# SD_Card.net
KiCad netlist of a schematic drawn in Altium Designer
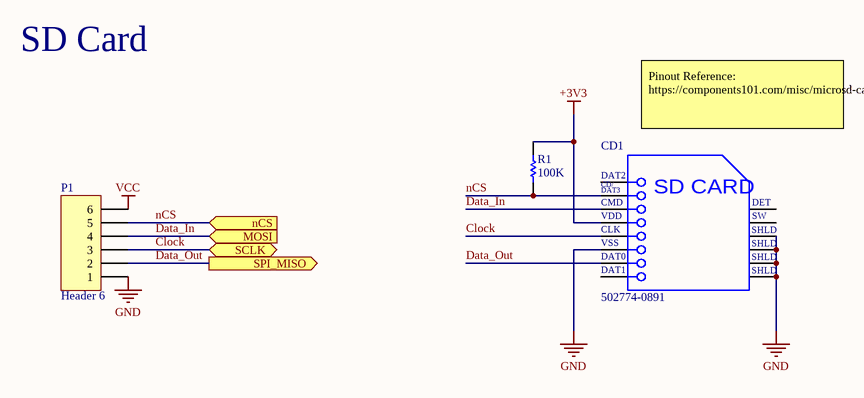
[diagram p0: SD_Card.SchDoc]

(export (version "E")
  (design (tool "Eeschema 10.0.6"))
  (components
    (comp (ref "CD1")
      (value "502774-0891")
      (footprint "MOLX-502774-0891_V")
      (description "Micro SD Memory Card Connector, 0.5 A, 10 V (DC), -25 to 85 degC, 8-Pin SMT, RoHS, Tape and Reel")
      (fields (field (name "MANUFACTURER") "Molex"))
      (libsource (lib "Altium Content Vault") (part "CN-SD-8-2SW-4S_B"))
    )
    (comp (ref "P1")
      (value "Header 6")
      (footprint "HDR1X6")
      (description "Header, 6-Pin")
      (fields (field (name "PUBLISHER") "Altium Limited"))
      (libsource (lib "Miscellaneous Connectors") (part "Header 6"))
    )
    (comp (ref "R1")
      (value "100K")
      (footprint "RESC1608X55X25ML10T15")
      (description "Chip Resistor, 100 KOhm, +/- 1%, 0.1 W, -55 to 155 degC, 0603 (1608 Metric), RoHS, Tape and Reel")
      (fields (field (name "MANUFACTURER") "Yageo") (field (name "TOLERANCE") "1%"))
      (libsource (lib "Altium Content Vault") (part "RES-2"))
    )
  )
  (nets
    (net (code "1") (name "+3V3") (class "Default")
      (node (ref "CD1") (pin "4") (pinfunction "VDD_4") (pintype "passive"))
      (node (ref "R1") (pin "2") (pinfunction "2_2") (pintype "passive"))
    )
    (net (code "2") (name "/Clock") (class "Default")
      (node (ref "CD1") (pin "5") (pinfunction "CLK_5") (pintype "passive"))
      (node (ref "P1") (pin "3") (pinfunction "3_3") (pintype "passive"))
    )
    (net (code "3") (name "/Data_In") (class "Default")
      (node (ref "CD1") (pin "3") (pinfunction "CMD_3") (pintype "passive"))
      (node (ref "P1") (pin "4") (pinfunction "4_4") (pintype "passive"))
    )
    (net (code "4") (name "/Data_Out") (class "Default")
      (node (ref "CD1") (pin "7") (pinfunction "DAT0_7") (pintype "passive"))
      (node (ref "P1") (pin "2") (pinfunction "2_2") (pintype "passive"))
    )
    (net (code "5") (name "/nCS") (class "Default")
      (node (ref "CD1") (pin "2") (pinfunction "CD/DAT3_2") (pintype "passive"))
      (node (ref "P1") (pin "5") (pinfunction "5_5") (pintype "passive"))
      (node (ref "R1") (pin "1") (pinfunction "1_1") (pintype "passive"))
    )
    (net (code "6") (name "GND") (class "Default")
      (node (ref "CD1") (pin "11") (pinfunction "SHLD_11") (pintype "passive"))
      (node (ref "CD1") (pin "12") (pinfunction "SHLD_12") (pintype "passive"))
      (node (ref "CD1") (pin "13") (pinfunction "SHLD_13") (pintype "passive"))
      (node (ref "CD1") (pin "14") (pinfunction "SHLD_14") (pintype "passive"))
      (node (ref "CD1") (pin "6") (pinfunction "VSS_6") (pintype "passive"))
      (node (ref "P1") (pin "1") (pinfunction "1_1") (pintype "passive"))
    )
    (net (code "7") (name "VCC") (class "Default")
      (node (ref "P1") (pin "6") (pinfunction "6_6") (pintype "passive"))
    )
    (net (code "8") (name "unconnected-(CD1-DAT1-Pad8)") (class "Default")
      (node (ref "CD1") (pin "8") (pinfunction "DAT1_8") (pintype "passive"))
    )
    (net (code "9") (name "unconnected-(CD1-DAT2-Pad1)") (class "Default")
      (node (ref "CD1") (pin "1") (pinfunction "DAT2_1") (pintype "passive"))
    )
    (net (code "10") (name "unconnected-(CD1-DETECT-Pad9)") (class "Default")
      (node (ref "CD1") (pin "9") (pinfunction "DETECT_9") (pintype "passive"))
    )
    (net (code "11") (name "unconnected-(CD1-SWITCH-Pad10)") (class "Default")
      (node (ref "CD1") (pin "10") (pinfunction "SWITCH_10") (pintype "passive"))
    )
  )
)
